# WH-MDC05F3E5_comm_v2_0.net
KiCad netlist of a schematic drawn in EAGLE
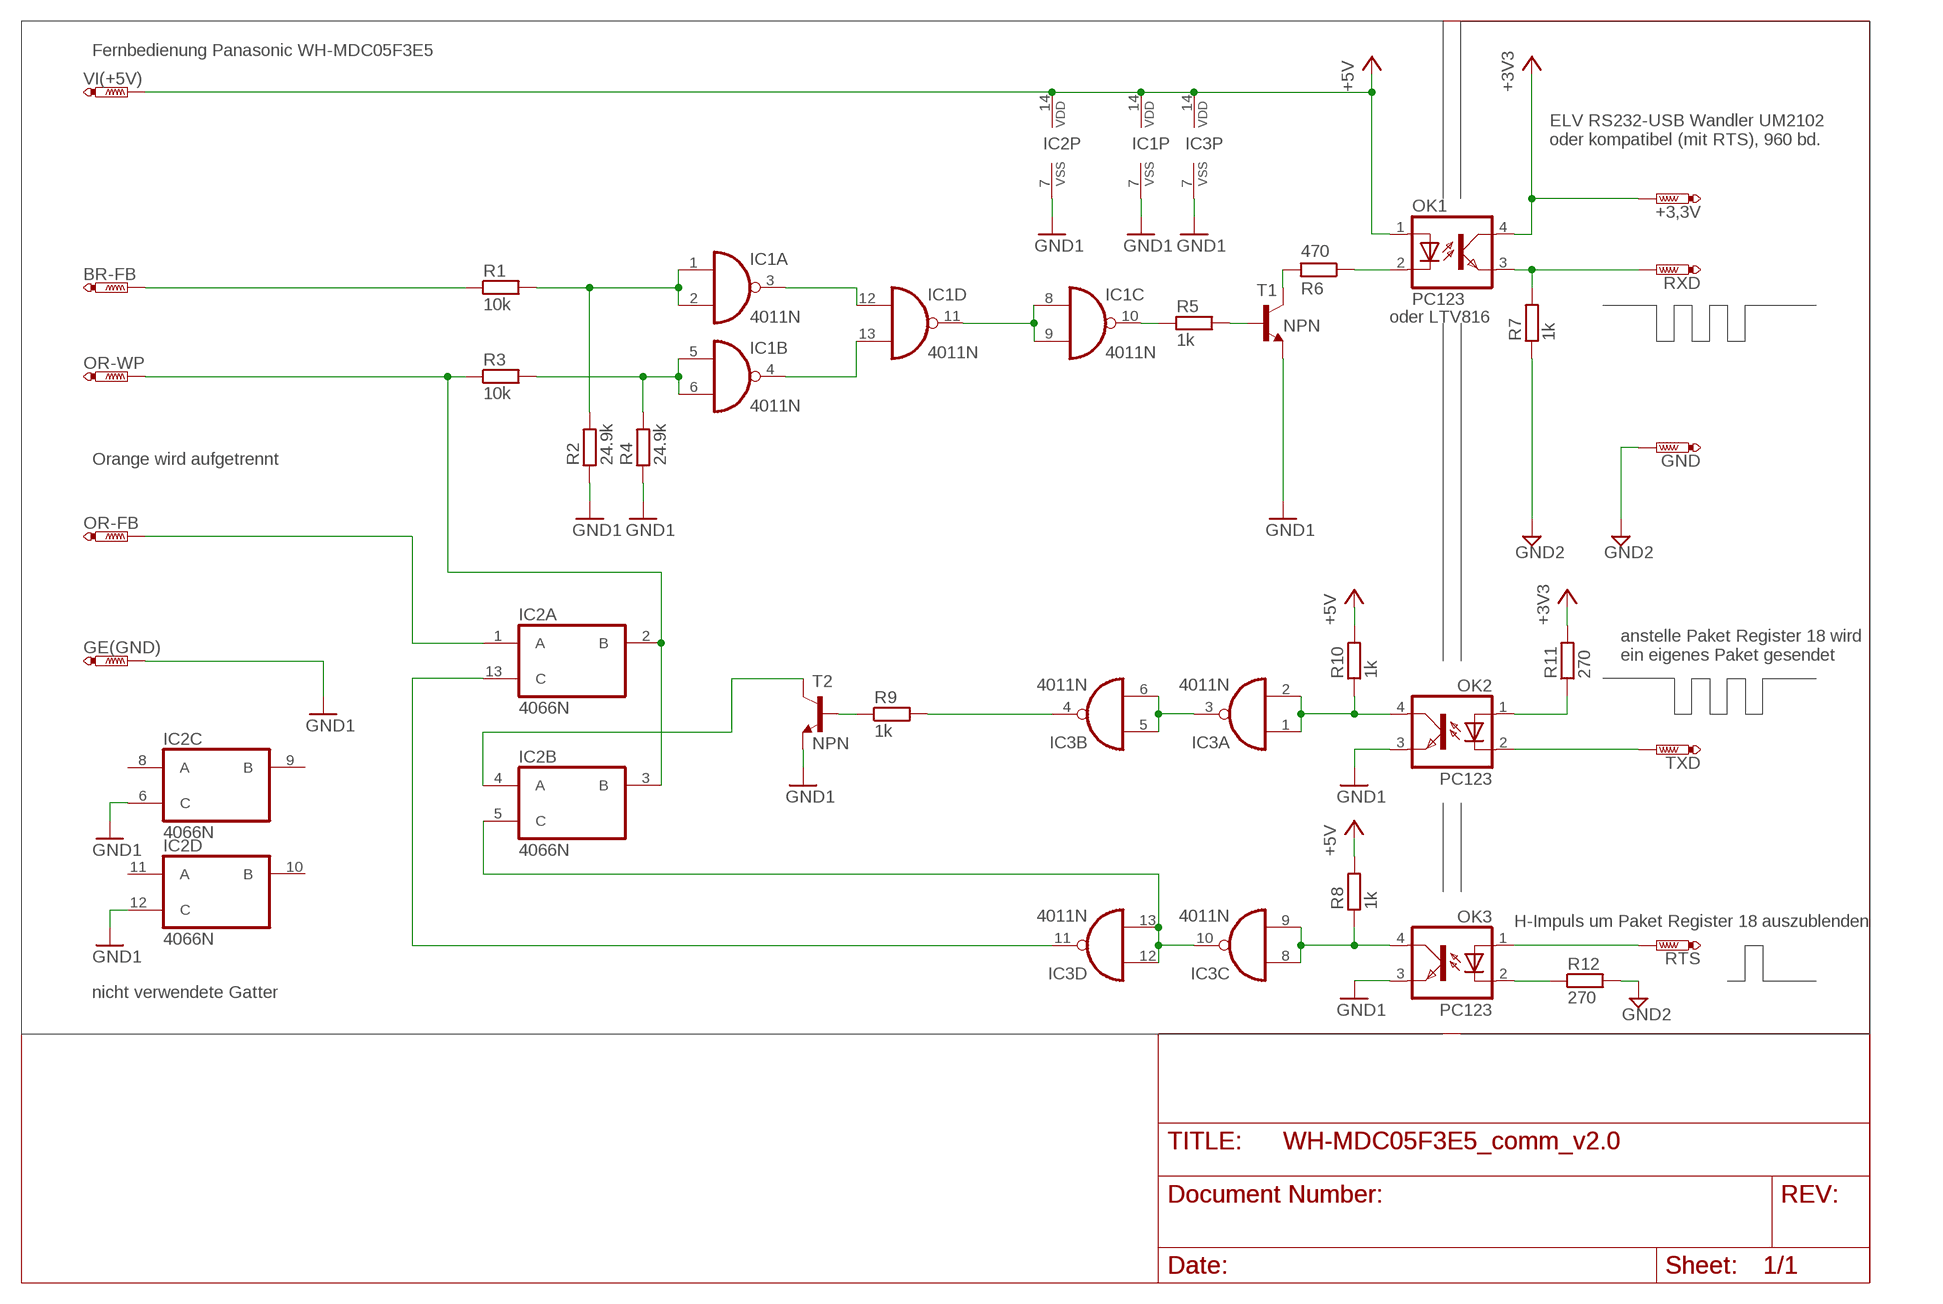
[diagram p0: schematic, sheet 1]

(export (version "E")
  (design (tool "Eeschema 10.0.6"))
  (components
    (comp (ref "+3,3V")
      (value "PTR1PAD1-17")
      (footprint "eagle-import:P1-17")
      (libsource (lib "eagle-import") (part "PTR1PAD1-17"))
    )
    (comp (ref "BR-FB")
      (value "PTR1PAD1-17")
      (footprint "eagle-import:P1-17")
      (libsource (lib "eagle-import") (part "PTR1PAD1-17"))
    )
    (comp (ref "GE(GND)")
      (value "PTR1PAD1-17")
      (footprint "eagle-import:P1-17")
      (libsource (lib "eagle-import") (part "PTR1PAD1-17"))
    )
    (comp (ref "GND")
      (value "PTR1PAD1-17")
      (footprint "eagle-import:P1-17")
      (libsource (lib "eagle-import") (part "PTR1PAD1-17"))
    )
    (comp (ref "IC1")
      (value "4011N")
      (footprint "eagle-import:DIL14")
      (libsource (lib "eagle-import") (part "4011N"))
    )
    (comp (ref "IC2")
      (value "4066N")
      (footprint "eagle-import:DIL14")
      (libsource (lib "eagle-import") (part "4066N"))
    )
    (comp (ref "IC3")
      (value "4011N")
      (footprint "eagle-import:DIL14")
      (libsource (lib "eagle-import") (part "4011N"))
    )
    (comp (ref "OK1")
      (value "PC123")
      (footprint "eagle-import:DIL04")
      (fields (field (name "MPN") "PC817X4J000F"))
      (libsource (lib "eagle-import") (part "PC817"))
    )
    (comp (ref "OK2")
      (value "PC123")
      (footprint "eagle-import:DIL04")
      (fields (field (name "MPN") "PC817X4J000F"))
      (libsource (lib "eagle-import") (part "PC817"))
    )
    (comp (ref "OK3")
      (value "PC123")
      (footprint "eagle-import:DIL04")
      (fields (field (name "MPN") "PC817X4J000F"))
      (libsource (lib "eagle-import") (part "PC817"))
    )
    (comp (ref "OR-FB")
      (value "PTR1PAD1-17")
      (footprint "eagle-import:P1-17")
      (libsource (lib "eagle-import") (part "PTR1PAD1-17"))
    )
    (comp (ref "OR-WP")
      (value "PTR1PAD1-17")
      (footprint "eagle-import:P1-17")
      (libsource (lib "eagle-import") (part "PTR1PAD1-17"))
    )
    (comp (ref "R1")
      (value "10k")
      (footprint "eagle-import:0207_10")
      (libsource (lib "eagle-import") (part "R-EU_0207/10"))
    )
    (comp (ref "R2")
      (value "24.9k")
      (footprint "eagle-import:0207_10")
      (libsource (lib "eagle-import") (part "R-EU_0207/10"))
    )
    (comp (ref "R3")
      (value "10k")
      (footprint "eagle-import:0207_10")
      (libsource (lib "eagle-import") (part "R-EU_0207/10"))
    )
    (comp (ref "R4")
      (value "24.9k")
      (footprint "eagle-import:0207_10")
      (libsource (lib "eagle-import") (part "R-EU_0207/10"))
    )
    (comp (ref "R5")
      (value "1k")
      (footprint "eagle-import:0207_10")
      (libsource (lib "eagle-import") (part "R-EU_0207/10"))
    )
    (comp (ref "R6")
      (value "470")
      (footprint "eagle-import:0207_10")
      (libsource (lib "eagle-import") (part "R-EU_0207/10"))
    )
    (comp (ref "R7")
      (value "1k")
      (footprint "eagle-import:0207_10")
      (libsource (lib "eagle-import") (part "R-EU_0207/10"))
    )
    (comp (ref "R8")
      (value "1k")
      (footprint "eagle-import:0207_7")
      (libsource (lib "eagle-import") (part "R-EU_0207/7"))
    )
    (comp (ref "R9")
      (value "1k")
      (footprint "eagle-import:0207_10")
      (libsource (lib "eagle-import") (part "R-EU_0207/10"))
    )
    (comp (ref "R10")
      (value "1k")
      (footprint "eagle-import:0207_7")
      (libsource (lib "eagle-import") (part "R-EU_0207/7"))
    )
    (comp (ref "R11")
      (value "270")
      (footprint "eagle-import:0207_7")
      (libsource (lib "eagle-import") (part "R-EU_0207/7"))
    )
    (comp (ref "R12")
      (value "270")
      (footprint "eagle-import:0207_7")
      (libsource (lib "eagle-import") (part "R-EU_0207/7"))
    )
    (comp (ref "RTS")
      (value "PTR1PAD1-17")
      (footprint "eagle-import:P1-17")
      (libsource (lib "eagle-import") (part "PTR1PAD1-17"))
    )
    (comp (ref "RXD")
      (value "PTR1PAD1-17")
      (footprint "eagle-import:P1-17")
      (libsource (lib "eagle-import") (part "PTR1PAD1-17"))
    )
    (comp (ref "T1")
      (value "NPN")
      (footprint "eagle-import:TO92-CBE")
      (libsource (lib "eagle-import") (part "-NPN-TO92-CBEBC547"))
    )
    (comp (ref "T2")
      (value "NPN")
      (footprint "eagle-import:TO92-CBE")
      (libsource (lib "eagle-import") (part "-NPN-TO92-CBEBC547"))
    )
    (comp (ref "TXD")
      (value "PTR1PAD1-17")
      (footprint "eagle-import:P1-17")
      (libsource (lib "eagle-import") (part "PTR1PAD1-17"))
    )
    (comp (ref "VI(+5V)")
      (value "PTR1PAD1-17")
      (footprint "eagle-import:P1-17")
      (libsource (lib "eagle-import") (part "PTR1PAD1-17"))
    )
  )
  (nets
    (net (code "1") (name "+3V3") (class "Default")
      (node (ref "+3,3V") (pin "TP") (pinfunction "TP_TP") (pintype "input"))
      (node (ref "OK1") (pin "4") (pinfunction "COL_4") (pintype "passive"))
      (node (ref "R11") (pin "2") (pinfunction "2_2") (pintype "passive"))
    )
    (net (code "2") (name "+5V") (class "Default")
      (node (ref "IC1") (pin "14") (pinfunction "VDD_14") (pintype "power_in"))
      (node (ref "IC2") (pin "14") (pinfunction "VDD_14") (pintype "power_in"))
      (node (ref "IC3") (pin "14") (pinfunction "VDD_14") (pintype "power_in"))
      (node (ref "OK1") (pin "1") (pinfunction "A_1") (pintype "passive"))
      (node (ref "R10") (pin "2") (pinfunction "2_2") (pintype "passive"))
      (node (ref "R8") (pin "2") (pinfunction "2_2") (pintype "passive"))
      (node (ref "VI(+5V)") (pin "TP") (pinfunction "TP_TP") (pintype "input"))
    )
    (net (code "3") (name "GND1") (class "Default")
      (node (ref "GE(GND)") (pin "TP") (pinfunction "TP_TP") (pintype "input"))
      (node (ref "IC1") (pin "7") (pinfunction "VSS_7") (pintype "power_in"))
      (node (ref "IC2") (pin "12") (pinfunction "C_12") (pintype "input"))
      (node (ref "IC2") (pin "6") (pinfunction "C_6") (pintype "input"))
      (node (ref "IC2") (pin "7") (pinfunction "VSS_7") (pintype "power_in"))
      (node (ref "IC3") (pin "7") (pinfunction "VSS_7") (pintype "power_in"))
      (node (ref "OK2") (pin "3") (pinfunction "EMIT_3") (pintype "passive"))
      (node (ref "OK3") (pin "3") (pinfunction "EMIT_3") (pintype "passive"))
      (node (ref "R2") (pin "1") (pinfunction "1_1") (pintype "passive"))
      (node (ref "R4") (pin "1") (pinfunction "1_1") (pintype "passive"))
      (node (ref "T1") (pin "E") (pinfunction "E_E") (pintype "passive"))
      (node (ref "T2") (pin "E") (pinfunction "E_E") (pintype "passive"))
    )
    (net (code "4") (name "GND2") (class "Default")
      (node (ref "GND") (pin "TP") (pinfunction "TP_TP") (pintype "input"))
      (node (ref "R12") (pin "2") (pinfunction "2_2") (pintype "passive"))
      (node (ref "R7") (pin "1") (pinfunction "1_1") (pintype "passive"))
    )
    (net (code "5") (name "Net-(BR-FB-PadTP)") (class "Default")
      (node (ref "BR-FB") (pin "TP") (pinfunction "TP_TP") (pintype "input"))
      (node (ref "R1") (pin "1") (pinfunction "1_1") (pintype "passive"))
    )
    (net (code "6") (name "Net-(IC1A-I0)") (class "Default")
      (node (ref "IC1") (pin "1") (pinfunction "I0_1") (pintype "input"))
      (node (ref "IC1") (pin "2") (pinfunction "I1_2") (pintype "input"))
      (node (ref "R1") (pin "2") (pinfunction "2_2") (pintype "passive"))
      (node (ref "R2") (pin "2") (pinfunction "2_2") (pintype "passive"))
    )
    (net (code "7") (name "Net-(IC1A-O)") (class "Default")
      (node (ref "IC1") (pin "12") (pinfunction "I0_12") (pintype "input"))
      (node (ref "IC1") (pin "3") (pinfunction "O_3") (pintype "output"))
    )
    (net (code "8") (name "Net-(IC1B-I0)") (class "Default")
      (node (ref "IC1") (pin "5") (pinfunction "I0_5") (pintype "input"))
      (node (ref "IC1") (pin "6") (pinfunction "I1_6") (pintype "input"))
      (node (ref "R3") (pin "2") (pinfunction "2_2") (pintype "passive"))
      (node (ref "R4") (pin "2") (pinfunction "2_2") (pintype "passive"))
    )
    (net (code "9") (name "Net-(IC1B-O)") (class "Default")
      (node (ref "IC1") (pin "13") (pinfunction "I1_13") (pintype "input"))
      (node (ref "IC1") (pin "4") (pinfunction "O_4") (pintype "output"))
    )
    (net (code "10") (name "Net-(IC1C-I0)") (class "Default")
      (node (ref "IC1") (pin "11") (pinfunction "O_11") (pintype "output"))
      (node (ref "IC1") (pin "8") (pinfunction "I0_8") (pintype "input"))
      (node (ref "IC1") (pin "9") (pinfunction "I1_9") (pintype "input"))
    )
    (net (code "11") (name "Net-(IC1C-O)") (class "Default")
      (node (ref "IC1") (pin "10") (pinfunction "O_10") (pintype "output"))
      (node (ref "R5") (pin "1") (pinfunction "1_1") (pintype "passive"))
    )
    (net (code "12") (name "Net-(IC2A-A)") (class "Default")
      (node (ref "IC2") (pin "1") (pinfunction "A_1") (pintype "tri_state"))
      (node (ref "OR-FB") (pin "TP") (pinfunction "TP_TP") (pintype "input"))
    )
    (net (code "13") (name "Net-(IC2A-B)") (class "Default")
      (node (ref "IC2") (pin "2") (pinfunction "B_2") (pintype "tri_state"))
      (node (ref "IC2") (pin "3") (pinfunction "B_3") (pintype "tri_state"))
      (node (ref "OR-WP") (pin "TP") (pinfunction "TP_TP") (pintype "input"))
      (node (ref "R3") (pin "1") (pinfunction "1_1") (pintype "passive"))
    )
    (net (code "14") (name "Net-(IC2A-C)") (class "Default")
      (node (ref "IC2") (pin "13") (pinfunction "C_13") (pintype "input"))
      (node (ref "IC3") (pin "11") (pinfunction "O_11") (pintype "output"))
    )
    (net (code "15") (name "Net-(IC2B-A)") (class "Default")
      (node (ref "IC2") (pin "4") (pinfunction "A_4") (pintype "tri_state"))
      (node (ref "T2") (pin "C") (pinfunction "C_C") (pintype "passive"))
    )
    (net (code "16") (name "Net-(IC2B-C)") (class "Default")
      (node (ref "IC2") (pin "5") (pinfunction "C_5") (pintype "input"))
      (node (ref "IC3") (pin "10") (pinfunction "O_10") (pintype "output"))
      (node (ref "IC3") (pin "12") (pinfunction "I0_12") (pintype "input"))
      (node (ref "IC3") (pin "13") (pinfunction "I1_13") (pintype "input"))
    )
    (net (code "17") (name "Net-(IC3A-I0)") (class "Default")
      (node (ref "IC3") (pin "1") (pinfunction "I0_1") (pintype "input"))
      (node (ref "IC3") (pin "2") (pinfunction "I1_2") (pintype "input"))
      (node (ref "OK2") (pin "4") (pinfunction "COL_4") (pintype "passive"))
      (node (ref "R10") (pin "1") (pinfunction "1_1") (pintype "passive"))
    )
    (net (code "18") (name "Net-(IC3A-O)") (class "Default")
      (node (ref "IC3") (pin "3") (pinfunction "O_3") (pintype "output"))
      (node (ref "IC3") (pin "5") (pinfunction "I0_5") (pintype "input"))
      (node (ref "IC3") (pin "6") (pinfunction "I1_6") (pintype "input"))
    )
    (net (code "19") (name "Net-(IC3B-O)") (class "Default")
      (node (ref "IC3") (pin "4") (pinfunction "O_4") (pintype "output"))
      (node (ref "R9") (pin "2") (pinfunction "2_2") (pintype "passive"))
    )
    (net (code "20") (name "Net-(IC3C-I0)") (class "Default")
      (node (ref "IC3") (pin "8") (pinfunction "I0_8") (pintype "input"))
      (node (ref "IC3") (pin "9") (pinfunction "I1_9") (pintype "input"))
      (node (ref "OK3") (pin "4") (pinfunction "COL_4") (pintype "passive"))
      (node (ref "R8") (pin "1") (pinfunction "1_1") (pintype "passive"))
    )
    (net (code "21") (name "Net-(OK1-C)") (class "Default")
      (node (ref "OK1") (pin "2") (pinfunction "C_2") (pintype "passive"))
      (node (ref "R6") (pin "1") (pinfunction "1_1") (pintype "passive"))
    )
    (net (code "22") (name "Net-(OK1-EMIT)") (class "Default")
      (node (ref "OK1") (pin "3") (pinfunction "EMIT_3") (pintype "passive"))
      (node (ref "R7") (pin "2") (pinfunction "2_2") (pintype "passive"))
      (node (ref "RXD") (pin "TP") (pinfunction "TP_TP") (pintype "input"))
    )
    (net (code "23") (name "Net-(OK2-A)") (class "Default")
      (node (ref "OK2") (pin "1") (pinfunction "A_1") (pintype "passive"))
      (node (ref "R11") (pin "1") (pinfunction "1_1") (pintype "passive"))
    )
    (net (code "24") (name "Net-(OK2-C)") (class "Default")
      (node (ref "OK2") (pin "2") (pinfunction "C_2") (pintype "passive"))
      (node (ref "TXD") (pin "TP") (pinfunction "TP_TP") (pintype "input"))
    )
    (net (code "25") (name "Net-(OK3-A)") (class "Default")
      (node (ref "OK3") (pin "1") (pinfunction "A_1") (pintype "passive"))
      (node (ref "RTS") (pin "TP") (pinfunction "TP_TP") (pintype "input"))
    )
    (net (code "26") (name "Net-(OK3-C)") (class "Default")
      (node (ref "OK3") (pin "2") (pinfunction "C_2") (pintype "passive"))
      (node (ref "R12") (pin "1") (pinfunction "1_1") (pintype "passive"))
    )
    (net (code "27") (name "Net-(R5-Pad2)") (class "Default")
      (node (ref "R5") (pin "2") (pinfunction "2_2") (pintype "passive"))
      (node (ref "T1") (pin "B") (pinfunction "B_B") (pintype "passive"))
    )
    (net (code "28") (name "Net-(R6-Pad2)") (class "Default")
      (node (ref "R6") (pin "2") (pinfunction "2_2") (pintype "passive"))
      (node (ref "T1") (pin "C") (pinfunction "C_C") (pintype "passive"))
    )
    (net (code "29") (name "Net-(R9-Pad1)") (class "Default")
      (node (ref "R9") (pin "1") (pinfunction "1_1") (pintype "passive"))
      (node (ref "T2") (pin "B") (pinfunction "B_B") (pintype "passive"))
    )
    (net (code "30") (name "unconnected-(IC2C-A-Pad8)") (class "Default")
      (node (ref "IC2") (pin "8") (pinfunction "A_8") (pintype "tri_state"))
    )
    (net (code "31") (name "unconnected-(IC2C-B-Pad9)") (class "Default")
      (node (ref "IC2") (pin "9") (pinfunction "B_9") (pintype "tri_state"))
    )
    (net (code "32") (name "unconnected-(IC2D-A-Pad11)") (class "Default")
      (node (ref "IC2") (pin "11") (pinfunction "A_11") (pintype "tri_state"))
    )
    (net (code "33") (name "unconnected-(IC2D-B-Pad10)") (class "Default")
      (node (ref "IC2") (pin "10") (pinfunction "B_10") (pintype "tri_state"))
    )
  )
)
